# OpenSalinity_v02.net
KiCad netlist of a schematic drawn in EAGLE
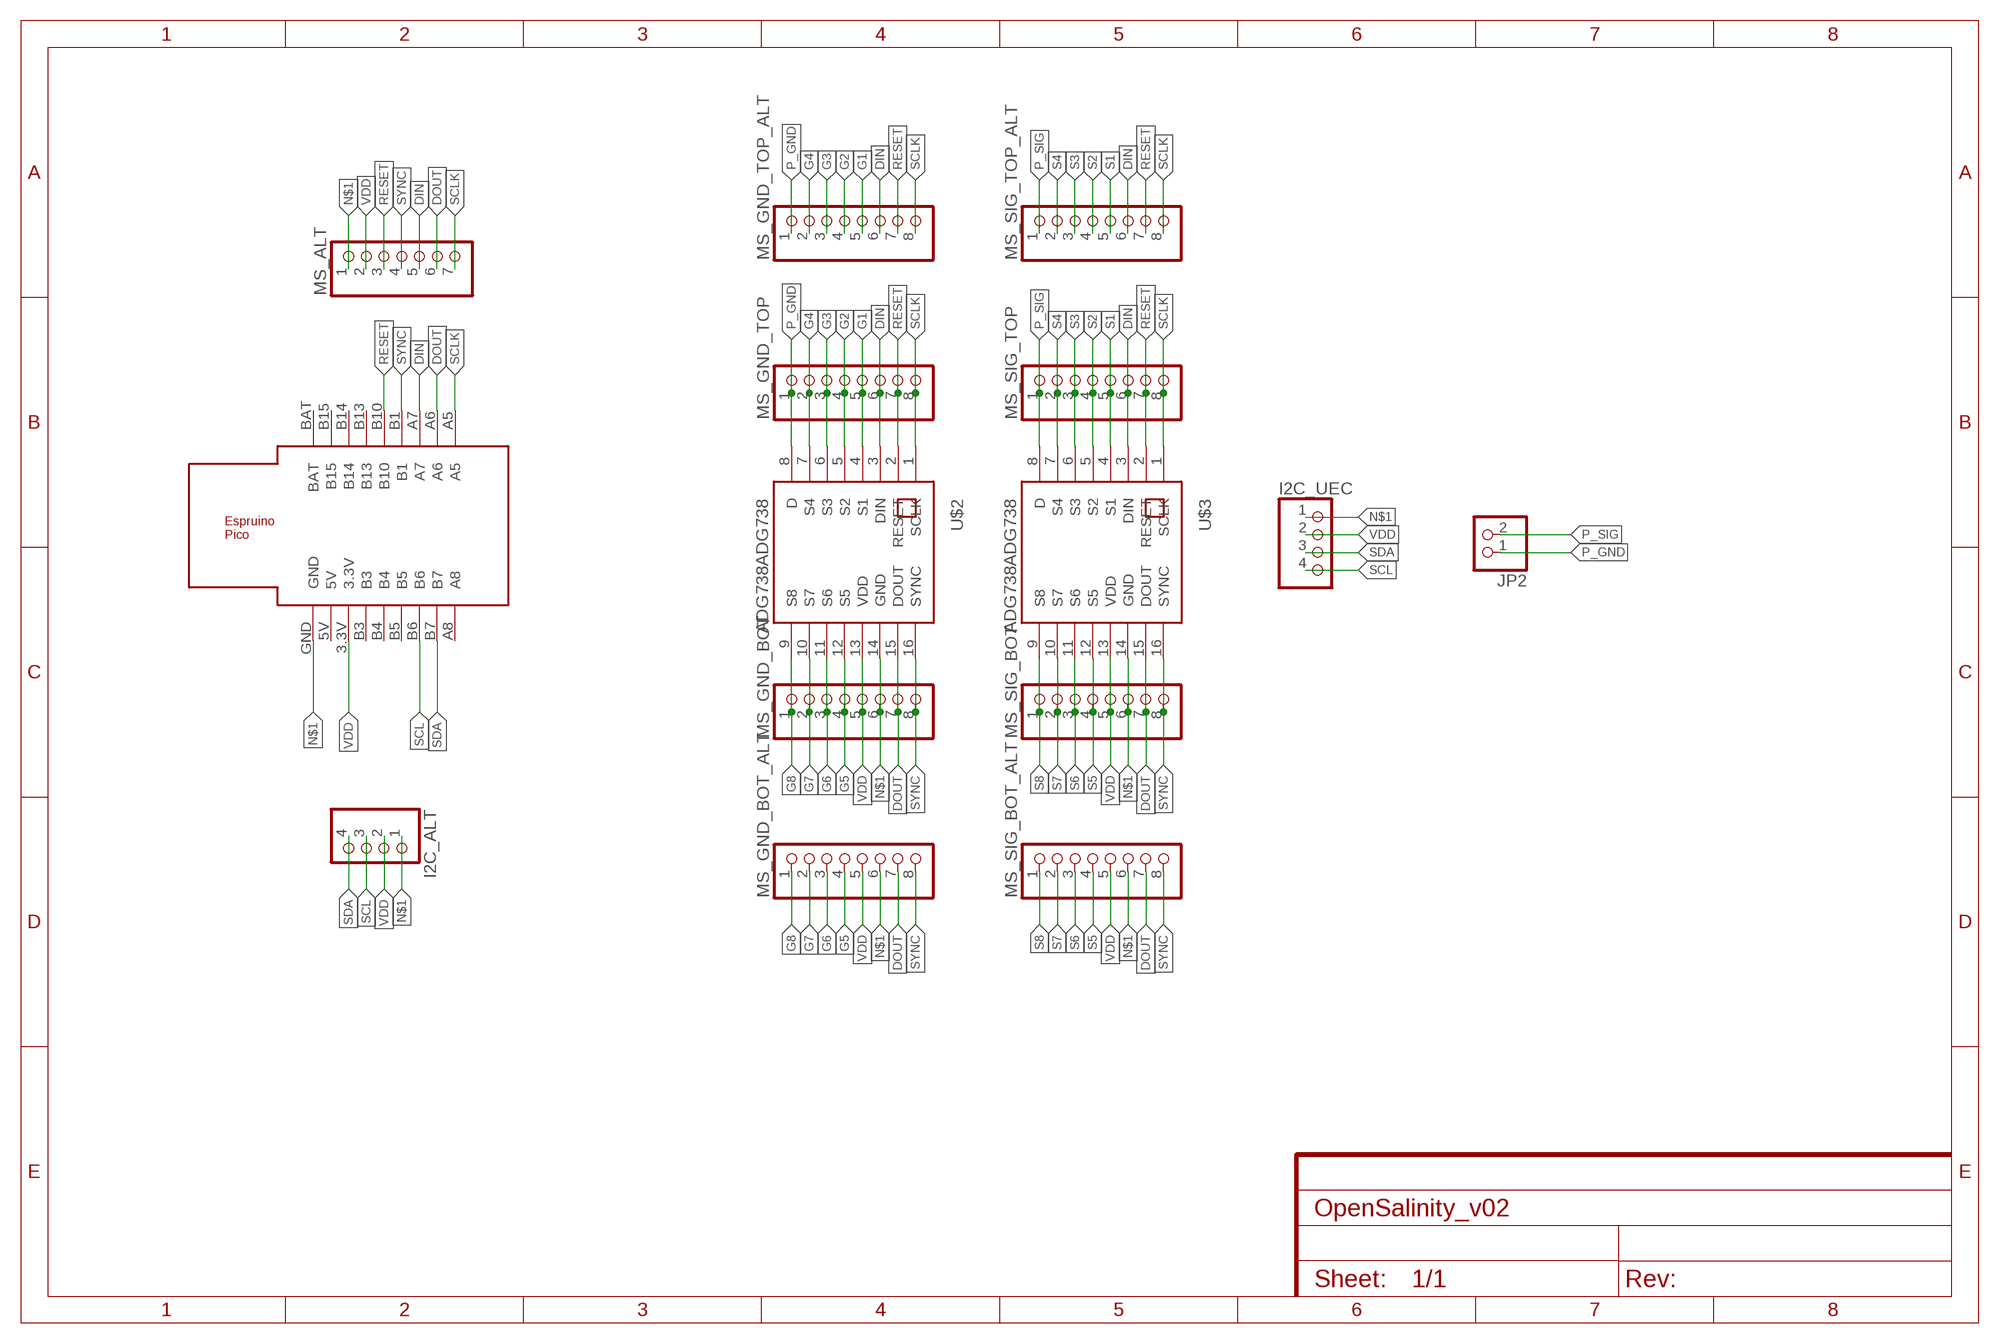
[diagram p0: schematic, sheet 1]

(export (version "E")
  (design (tool "Eeschema 10.0.6"))
  (components
    (comp (ref "I2C_ALT")
      (value "PINHD-1X4")
      (footprint "eagle-import:1X04")
      (libsource (lib "eagle-import") (part "PINHD-1X4"))
    )
    (comp (ref "I2C_UEC")
      (value "PINHD-1X4")
      (footprint "eagle-import:1X04")
      (libsource (lib "eagle-import") (part "PINHD-1X4"))
    )
    (comp (ref "JP2")
      (value "PINHD-1X2")
      (footprint "eagle-import:1X02")
      (libsource (lib "eagle-import") (part "PINHD-1X2"))
    )
    (comp (ref "MS_ALT")
      (value "PINHD-1X7")
      (footprint "eagle-import:1X07")
      (libsource (lib "eagle-import") (part "PINHD-1X7"))
    )
    (comp (ref "MS_GND_BOT")
      (value "PINHD-1X8")
      (footprint "eagle-import:1X08")
      (libsource (lib "eagle-import") (part "PINHD-1X8"))
    )
    (comp (ref "MS_GND_BOT_ALT")
      (value "PINHD-1X8")
      (footprint "eagle-import:1X08")
      (libsource (lib "eagle-import") (part "PINHD-1X8"))
    )
    (comp (ref "MS_GND_TOP")
      (value "PINHD-1X8")
      (footprint "eagle-import:1X08")
      (libsource (lib "eagle-import") (part "PINHD-1X8"))
    )
    (comp (ref "MS_GND_TOP_ALT")
      (value "PINHD-1X8")
      (footprint "eagle-import:1X08")
      (libsource (lib "eagle-import") (part "PINHD-1X8"))
    )
    (comp (ref "MS_SIG_BOT")
      (value "PINHD-1X8")
      (footprint "eagle-import:1X08")
      (libsource (lib "eagle-import") (part "PINHD-1X8"))
    )
    (comp (ref "MS_SIG_BOT_ALT")
      (value "PINHD-1X8")
      (footprint "eagle-import:1X08")
      (libsource (lib "eagle-import") (part "PINHD-1X8"))
    )
    (comp (ref "MS_SIG_TOP")
      (value "PINHD-1X8")
      (footprint "eagle-import:1X08")
      (libsource (lib "eagle-import") (part "PINHD-1X8"))
    )
    (comp (ref "MS_SIG_TOP_ALT")
      (value "PINHD-1X8")
      (footprint "eagle-import:1X08")
      (libsource (lib "eagle-import") (part "PINHD-1X8"))
    )
    (comp (ref "U$1")
      (value "ESPRUINO_PICO_0.1")
      (footprint "eagle-import:ESPRUINO_PICO_0.1")
      (libsource (lib "eagle-import") (part "ESPRUINO_PICO_0.1"))
    )
    (comp (ref "U$2")
      (value "ADG738ADG738")
      (footprint "eagle-import:TSSOP16")
      (libsource (lib "eagle-import") (part "ADG738ADG738"))
    )
    (comp (ref "U$3")
      (value "ADG738ADG738")
      (footprint "eagle-import:TSSOP16")
      (libsource (lib "eagle-import") (part "ADG738ADG738"))
    )
  )
  (nets
    (net (code "1") (name "DIN") (class "Default")
      (node (ref "MS_ALT") (pin "5") (pinfunction "5_5") (pintype "passive"))
      (node (ref "MS_GND_TOP") (pin "6") (pinfunction "6_6") (pintype "passive"))
      (node (ref "MS_GND_TOP_ALT") (pin "6") (pinfunction "6_6") (pintype "passive"))
      (node (ref "MS_SIG_TOP") (pin "6") (pinfunction "6_6") (pintype "passive"))
      (node (ref "MS_SIG_TOP_ALT") (pin "6") (pinfunction "6_6") (pintype "passive"))
      (node (ref "U$1") (pin "A7") (pinfunction "A7_A7") (pintype "bidirectional"))
      (node (ref "U$2") (pin "3") (pinfunction "DIN_3") (pintype "bidirectional"))
      (node (ref "U$3") (pin "3") (pinfunction "DIN_3") (pintype "bidirectional"))
    )
    (net (code "2") (name "DOUT") (class "Default")
      (node (ref "MS_ALT") (pin "6") (pinfunction "6_6") (pintype "passive"))
      (node (ref "MS_GND_BOT") (pin "7") (pinfunction "7_7") (pintype "passive"))
      (node (ref "MS_GND_BOT_ALT") (pin "7") (pinfunction "7_7") (pintype "passive"))
      (node (ref "MS_SIG_BOT") (pin "7") (pinfunction "7_7") (pintype "passive"))
      (node (ref "MS_SIG_BOT_ALT") (pin "7") (pinfunction "7_7") (pintype "passive"))
      (node (ref "U$1") (pin "A6") (pinfunction "A6_A6") (pintype "bidirectional"))
      (node (ref "U$2") (pin "15") (pinfunction "DOUT_15") (pintype "bidirectional"))
      (node (ref "U$3") (pin "15") (pinfunction "DOUT_15") (pintype "bidirectional"))
    )
    (net (code "3") (name "G1") (class "Default")
      (node (ref "MS_GND_TOP") (pin "5") (pinfunction "5_5") (pintype "passive"))
      (node (ref "MS_GND_TOP_ALT") (pin "5") (pinfunction "5_5") (pintype "passive"))
      (node (ref "U$2") (pin "4") (pinfunction "S1_4") (pintype "bidirectional"))
    )
    (net (code "4") (name "G2") (class "Default")
      (node (ref "MS_GND_TOP") (pin "4") (pinfunction "4_4") (pintype "passive"))
      (node (ref "MS_GND_TOP_ALT") (pin "4") (pinfunction "4_4") (pintype "passive"))
      (node (ref "U$2") (pin "5") (pinfunction "S2_5") (pintype "bidirectional"))
    )
    (net (code "5") (name "G3") (class "Default")
      (node (ref "MS_GND_TOP") (pin "3") (pinfunction "3_3") (pintype "passive"))
      (node (ref "MS_GND_TOP_ALT") (pin "3") (pinfunction "3_3") (pintype "passive"))
      (node (ref "U$2") (pin "6") (pinfunction "S3_6") (pintype "bidirectional"))
    )
    (net (code "6") (name "G4") (class "Default")
      (node (ref "MS_GND_TOP") (pin "2") (pinfunction "2_2") (pintype "passive"))
      (node (ref "MS_GND_TOP_ALT") (pin "2") (pinfunction "2_2") (pintype "passive"))
      (node (ref "U$2") (pin "7") (pinfunction "S4_7") (pintype "bidirectional"))
    )
    (net (code "7") (name "G5") (class "Default")
      (node (ref "MS_GND_BOT") (pin "4") (pinfunction "4_4") (pintype "passive"))
      (node (ref "MS_GND_BOT_ALT") (pin "4") (pinfunction "4_4") (pintype "passive"))
      (node (ref "U$2") (pin "12") (pinfunction "S5_12") (pintype "bidirectional"))
    )
    (net (code "8") (name "G6") (class "Default")
      (node (ref "MS_GND_BOT") (pin "3") (pinfunction "3_3") (pintype "passive"))
      (node (ref "MS_GND_BOT_ALT") (pin "3") (pinfunction "3_3") (pintype "passive"))
      (node (ref "U$2") (pin "11") (pinfunction "S6_11") (pintype "bidirectional"))
    )
    (net (code "9") (name "G7") (class "Default")
      (node (ref "MS_GND_BOT") (pin "2") (pinfunction "2_2") (pintype "passive"))
      (node (ref "MS_GND_BOT_ALT") (pin "2") (pinfunction "2_2") (pintype "passive"))
      (node (ref "U$2") (pin "10") (pinfunction "S7_10") (pintype "bidirectional"))
    )
    (net (code "10") (name "G8") (class "Default")
      (node (ref "MS_GND_BOT") (pin "1") (pinfunction "1_1") (pintype "passive"))
      (node (ref "MS_GND_BOT_ALT") (pin "1") (pinfunction "1_1") (pintype "passive"))
      (node (ref "U$2") (pin "9") (pinfunction "S8_9") (pintype "bidirectional"))
    )
    (net (code "11") (name "N$1") (class "Default")
      (node (ref "I2C_ALT") (pin "1") (pinfunction "1_1") (pintype "passive"))
      (node (ref "I2C_UEC") (pin "1") (pinfunction "1_1") (pintype "passive"))
      (node (ref "MS_ALT") (pin "1") (pinfunction "1_1") (pintype "passive"))
      (node (ref "MS_GND_BOT") (pin "6") (pinfunction "6_6") (pintype "passive"))
      (node (ref "MS_GND_BOT_ALT") (pin "6") (pinfunction "6_6") (pintype "passive"))
      (node (ref "MS_SIG_BOT") (pin "6") (pinfunction "6_6") (pintype "passive"))
      (node (ref "MS_SIG_BOT_ALT") (pin "6") (pinfunction "6_6") (pintype "passive"))
      (node (ref "U$1") (pin "GND") (pinfunction "GND_GND") (pintype "bidirectional"))
      (node (ref "U$2") (pin "14") (pinfunction "GND_14") (pintype "bidirectional"))
      (node (ref "U$3") (pin "14") (pinfunction "GND_14") (pintype "bidirectional"))
    )
    (net (code "12") (name "P_GND") (class "Default")
      (node (ref "JP2") (pin "1") (pinfunction "1_1") (pintype "passive"))
      (node (ref "MS_GND_TOP") (pin "1") (pinfunction "1_1") (pintype "passive"))
      (node (ref "MS_GND_TOP_ALT") (pin "1") (pinfunction "1_1") (pintype "passive"))
      (node (ref "U$2") (pin "8") (pinfunction "D_8") (pintype "bidirectional"))
    )
    (net (code "13") (name "P_SIG") (class "Default")
      (node (ref "JP2") (pin "2") (pinfunction "2_2") (pintype "passive"))
      (node (ref "MS_SIG_TOP") (pin "1") (pinfunction "1_1") (pintype "passive"))
      (node (ref "MS_SIG_TOP_ALT") (pin "1") (pinfunction "1_1") (pintype "passive"))
      (node (ref "U$3") (pin "8") (pinfunction "D_8") (pintype "bidirectional"))
    )
    (net (code "14") (name "RESET") (class "Default")
      (node (ref "MS_ALT") (pin "3") (pinfunction "3_3") (pintype "passive"))
      (node (ref "MS_GND_TOP") (pin "7") (pinfunction "7_7") (pintype "passive"))
      (node (ref "MS_GND_TOP_ALT") (pin "7") (pinfunction "7_7") (pintype "passive"))
      (node (ref "MS_SIG_TOP") (pin "7") (pinfunction "7_7") (pintype "passive"))
      (node (ref "MS_SIG_TOP_ALT") (pin "7") (pinfunction "7_7") (pintype "passive"))
      (node (ref "U$1") (pin "B10") (pinfunction "B10_B10") (pintype "bidirectional"))
      (node (ref "U$2") (pin "2") (pinfunction "RESET_2") (pintype "bidirectional"))
      (node (ref "U$3") (pin "2") (pinfunction "RESET_2") (pintype "bidirectional"))
    )
    (net (code "15") (name "S1") (class "Default")
      (node (ref "MS_SIG_TOP") (pin "5") (pinfunction "5_5") (pintype "passive"))
      (node (ref "MS_SIG_TOP_ALT") (pin "5") (pinfunction "5_5") (pintype "passive"))
      (node (ref "U$3") (pin "4") (pinfunction "S1_4") (pintype "bidirectional"))
    )
    (net (code "16") (name "S2") (class "Default")
      (node (ref "MS_SIG_TOP") (pin "4") (pinfunction "4_4") (pintype "passive"))
      (node (ref "MS_SIG_TOP_ALT") (pin "4") (pinfunction "4_4") (pintype "passive"))
      (node (ref "U$3") (pin "5") (pinfunction "S2_5") (pintype "bidirectional"))
    )
    (net (code "17") (name "S3") (class "Default")
      (node (ref "MS_SIG_TOP") (pin "3") (pinfunction "3_3") (pintype "passive"))
      (node (ref "MS_SIG_TOP_ALT") (pin "3") (pinfunction "3_3") (pintype "passive"))
      (node (ref "U$3") (pin "6") (pinfunction "S3_6") (pintype "bidirectional"))
    )
    (net (code "18") (name "S4") (class "Default")
      (node (ref "MS_SIG_TOP") (pin "2") (pinfunction "2_2") (pintype "passive"))
      (node (ref "MS_SIG_TOP_ALT") (pin "2") (pinfunction "2_2") (pintype "passive"))
      (node (ref "U$3") (pin "7") (pinfunction "S4_7") (pintype "bidirectional"))
    )
    (net (code "19") (name "S5") (class "Default")
      (node (ref "MS_SIG_BOT") (pin "4") (pinfunction "4_4") (pintype "passive"))
      (node (ref "MS_SIG_BOT_ALT") (pin "4") (pinfunction "4_4") (pintype "passive"))
      (node (ref "U$3") (pin "12") (pinfunction "S5_12") (pintype "bidirectional"))
    )
    (net (code "20") (name "S6") (class "Default")
      (node (ref "MS_SIG_BOT") (pin "3") (pinfunction "3_3") (pintype "passive"))
      (node (ref "MS_SIG_BOT_ALT") (pin "3") (pinfunction "3_3") (pintype "passive"))
      (node (ref "U$3") (pin "11") (pinfunction "S6_11") (pintype "bidirectional"))
    )
    (net (code "21") (name "S7") (class "Default")
      (node (ref "MS_SIG_BOT") (pin "2") (pinfunction "2_2") (pintype "passive"))
      (node (ref "MS_SIG_BOT_ALT") (pin "2") (pinfunction "2_2") (pintype "passive"))
      (node (ref "U$3") (pin "10") (pinfunction "S7_10") (pintype "bidirectional"))
    )
    (net (code "22") (name "S8") (class "Default")
      (node (ref "MS_SIG_BOT") (pin "1") (pinfunction "1_1") (pintype "passive"))
      (node (ref "MS_SIG_BOT_ALT") (pin "1") (pinfunction "1_1") (pintype "passive"))
      (node (ref "U$3") (pin "9") (pinfunction "S8_9") (pintype "bidirectional"))
    )
    (net (code "23") (name "SCL") (class "Default")
      (node (ref "I2C_ALT") (pin "3") (pinfunction "3_3") (pintype "passive"))
      (node (ref "I2C_UEC") (pin "4") (pinfunction "4_4") (pintype "passive"))
      (node (ref "U$1") (pin "B6") (pinfunction "B6_B6") (pintype "bidirectional"))
    )
    (net (code "24") (name "SCLK") (class "Default")
      (node (ref "MS_ALT") (pin "7") (pinfunction "7_7") (pintype "passive"))
      (node (ref "MS_GND_TOP") (pin "8") (pinfunction "8_8") (pintype "passive"))
      (node (ref "MS_GND_TOP_ALT") (pin "8") (pinfunction "8_8") (pintype "passive"))
      (node (ref "MS_SIG_TOP") (pin "8") (pinfunction "8_8") (pintype "passive"))
      (node (ref "MS_SIG_TOP_ALT") (pin "8") (pinfunction "8_8") (pintype "passive"))
      (node (ref "U$1") (pin "A5") (pinfunction "A5_A5") (pintype "bidirectional"))
      (node (ref "U$2") (pin "1") (pinfunction "SCLK_1") (pintype "bidirectional"))
      (node (ref "U$3") (pin "1") (pinfunction "SCLK_1") (pintype "bidirectional"))
    )
    (net (code "25") (name "SDA") (class "Default")
      (node (ref "I2C_ALT") (pin "4") (pinfunction "4_4") (pintype "passive"))
      (node (ref "I2C_UEC") (pin "3") (pinfunction "3_3") (pintype "passive"))
      (node (ref "U$1") (pin "B7") (pinfunction "B7_B7") (pintype "bidirectional"))
    )
    (net (code "26") (name "SYNC") (class "Default")
      (node (ref "MS_ALT") (pin "4") (pinfunction "4_4") (pintype "passive"))
      (node (ref "MS_GND_BOT") (pin "8") (pinfunction "8_8") (pintype "passive"))
      (node (ref "MS_GND_BOT_ALT") (pin "8") (pinfunction "8_8") (pintype "passive"))
      (node (ref "MS_SIG_BOT") (pin "8") (pinfunction "8_8") (pintype "passive"))
      (node (ref "MS_SIG_BOT_ALT") (pin "8") (pinfunction "8_8") (pintype "passive"))
      (node (ref "U$1") (pin "B1") (pinfunction "B1_B1") (pintype "bidirectional"))
      (node (ref "U$2") (pin "16") (pinfunction "SYNC_16") (pintype "bidirectional"))
      (node (ref "U$3") (pin "16") (pinfunction "SYNC_16") (pintype "bidirectional"))
    )
    (net (code "27") (name "VDD") (class "Default")
      (node (ref "I2C_ALT") (pin "2") (pinfunction "2_2") (pintype "passive"))
      (node (ref "I2C_UEC") (pin "2") (pinfunction "2_2") (pintype "passive"))
      (node (ref "MS_ALT") (pin "2") (pinfunction "2_2") (pintype "passive"))
      (node (ref "MS_GND_BOT") (pin "5") (pinfunction "5_5") (pintype "passive"))
      (node (ref "MS_GND_BOT_ALT") (pin "5") (pinfunction "5_5") (pintype "passive"))
      (node (ref "MS_SIG_BOT") (pin "5") (pinfunction "5_5") (pintype "passive"))
      (node (ref "MS_SIG_BOT_ALT") (pin "5") (pinfunction "5_5") (pintype "passive"))
      (node (ref "U$1") (pin "3.3V") (pinfunction "3.3V_3.3V") (pintype "bidirectional"))
      (node (ref "U$2") (pin "13") (pinfunction "VDD_13") (pintype "bidirectional"))
      (node (ref "U$3") (pin "13") (pinfunction "VDD_13") (pintype "bidirectional"))
    )
    (net (code "28") (name "unconnected-(U$1-Pad5V)") (class "Default")
      (node (ref "U$1") (pin "5V") (pinfunction "5V_5V") (pintype "bidirectional"))
    )
    (net (code "29") (name "unconnected-(U$1-PadA8)") (class "Default")
      (node (ref "U$1") (pin "A8") (pinfunction "A8_A8") (pintype "bidirectional"))
    )
    (net (code "30") (name "unconnected-(U$1-PadB3)") (class "Default")
      (node (ref "U$1") (pin "B3") (pinfunction "B3_B3") (pintype "bidirectional"))
    )
    (net (code "31") (name "unconnected-(U$1-PadB4)") (class "Default")
      (node (ref "U$1") (pin "B4") (pinfunction "B4_B4") (pintype "bidirectional"))
    )
    (net (code "32") (name "unconnected-(U$1-PadB5)") (class "Default")
      (node (ref "U$1") (pin "B5") (pinfunction "B5_B5") (pintype "bidirectional"))
    )
    (net (code "33") (name "unconnected-(U$1-PadB13)") (class "Default")
      (node (ref "U$1") (pin "B13") (pinfunction "B13_B13") (pintype "bidirectional"))
    )
    (net (code "34") (name "unconnected-(U$1-PadB14)") (class "Default")
      (node (ref "U$1") (pin "B14") (pinfunction "B14_B14") (pintype "bidirectional"))
    )
    (net (code "35") (name "unconnected-(U$1-PadB15)") (class "Default")
      (node (ref "U$1") (pin "B15") (pinfunction "B15_B15") (pintype "bidirectional"))
    )
    (net (code "36") (name "unconnected-(U$1-PadBAT)") (class "Default")
      (node (ref "U$1") (pin "BAT") (pinfunction "BAT_BAT") (pintype "bidirectional"))
    )
  )
)
